# Hello_Bomi.net
KiCad netlist of a schematic drawn in EAGLE
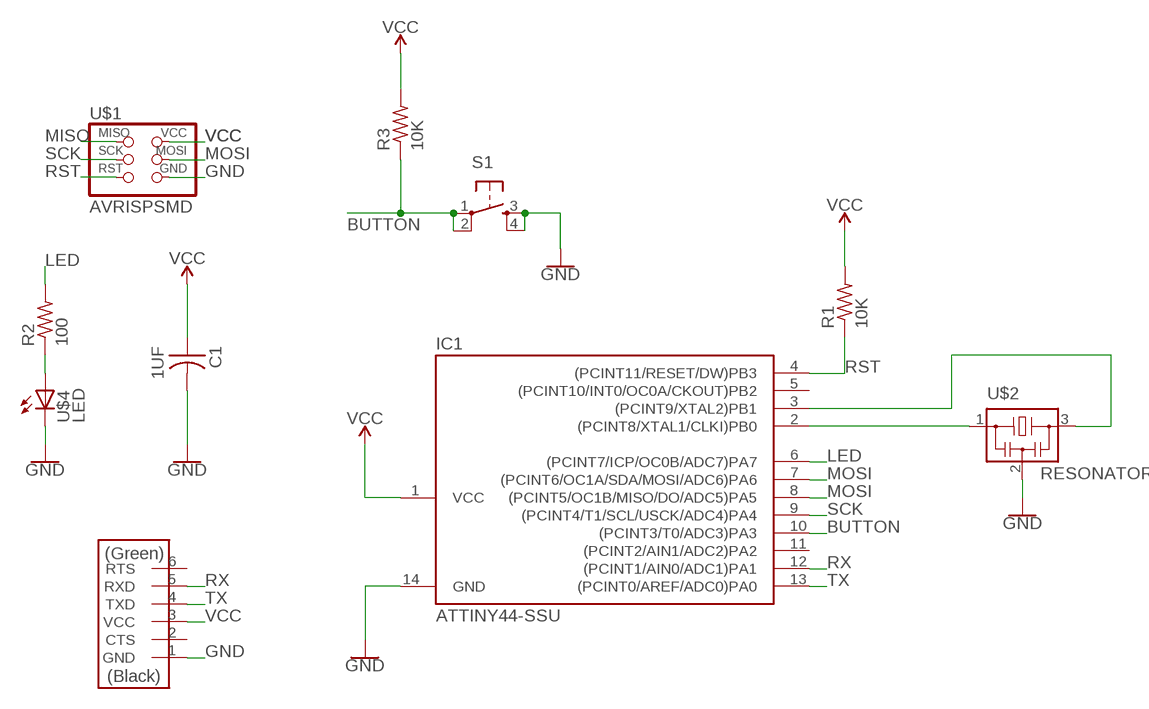
[diagram p0: schematic, sheet 1]

(export (version "E")
  (design (tool "Eeschema 10.0.6"))
  (components
    (comp (ref "C1")
      (value "1UF")
      (footprint "eagle-import:C1206FAB")
      (libsource (lib "eagle-import") (part "CAP-US1206FAB"))
    )
    (comp (ref "IC1")
      (value "ATTINY44-SSU")
      (footprint "eagle-import:SOIC14")
      (libsource (lib "eagle-import") (part "ATTINY44-SSU"))
    )
    (comp (ref "R1")
      (value "10K")
      (footprint "eagle-import:R1206FAB")
      (libsource (lib "eagle-import") (part "RES-US1206FAB"))
    )
    (comp (ref "R2")
      (value "100")
      (footprint "eagle-import:R1206FAB")
      (libsource (lib "eagle-import") (part "RES-US1206FAB"))
    )
    (comp (ref "R3")
      (value "10K")
      (footprint "eagle-import:R1206FAB")
      (libsource (lib "eagle-import") (part "RES-US1206FAB"))
    )
    (comp (ref "S1")
      (value "6MM_SWITCH6MM_SWITCH")
      (footprint "eagle-import:6MM_SWITCH")
      (libsource (lib "eagle-import") (part "6MM_SWITCH6MM_SWITCH"))
    )
    (comp (ref "U$1")
      (value "AVRISPSMD")
      (footprint "eagle-import:2X03SMD")
      (libsource (lib "eagle-import") (part "AVRISPSMD"))
    )
    (comp (ref "U$2")
      (value "RESONATOR")
      (footprint "eagle-import:EFOBM")
      (libsource (lib "eagle-import") (part "RESONATOR"))
    )
    (comp (ref "U$3")
      (value "FTDI-SMD-HEADER")
      (footprint "eagle-import:1X06SMD")
      (libsource (lib "eagle-import") (part "FTDI-SMD-HEADER"))
    )
    (comp (ref "U$4")
      (value "LED")
      (footprint "eagle-import:LED1206FAB")
      (libsource (lib "eagle-import") (part "LEDFAB1206"))
    )
  )
  (nets
    (net (code "1") (name "/BUTTON") (class "Default")
      (node (ref "IC1") (pin "10") (pinfunction "(PCINT3/T0/ADC3)PA3_10") (pintype "bidirectional"))
      (node (ref "R3") (pin "1") (pinfunction "1_1") (pintype "passive"))
      (node (ref "S1") (pin "1") (pinfunction "P_1") (pintype "passive"))
      (node (ref "S1") (pin "2") (pinfunction "P1_2") (pintype "passive"))
    )
    (net (code "2") (name "/LED") (class "Default")
      (node (ref "IC1") (pin "6") (pinfunction "(PCINT7/ICP/OC0B/ADC7)PA7_6") (pintype "bidirectional"))
      (node (ref "R2") (pin "2") (pinfunction "2_2") (pintype "passive"))
    )
    (net (code "3") (name "/MISO") (class "Default")
      (node (ref "U$1") (pin "1") (pinfunction "MISO_1") (pintype "passive"))
    )
    (net (code "4") (name "/MOSI") (class "Default")
      (node (ref "IC1") (pin "7") (pinfunction "(PCINT6/OC1A/SDA/MOSI/ADC6)PA6_7") (pintype "bidirectional"))
      (node (ref "IC1") (pin "8") (pinfunction "(PCINT5/OC1B/MISO/DO/ADC5)PA5_8") (pintype "bidirectional"))
      (node (ref "U$1") (pin "4") (pinfunction "MOSI_4") (pintype "passive"))
    )
    (net (code "5") (name "/RST") (class "Default")
      (node (ref "IC1") (pin "4") (pinfunction "(PCINT11/RESET/DW)PB3_4") (pintype "bidirectional"))
      (node (ref "R1") (pin "1") (pinfunction "1_1") (pintype "passive"))
      (node (ref "U$1") (pin "5") (pinfunction "RST_5") (pintype "passive"))
    )
    (net (code "6") (name "/RX") (class "Default")
      (node (ref "IC1") (pin "12") (pinfunction "(PCINT1/AIN0/ADC1)PA1_12") (pintype "bidirectional"))
      (node (ref "U$3") (pin "5") (pinfunction "RXD_5") (pintype "bidirectional"))
    )
    (net (code "7") (name "/SCK") (class "Default")
      (node (ref "IC1") (pin "9") (pinfunction "(PCINT4/T1/SCL/USCK/ADC4)PA4_9") (pintype "bidirectional"))
      (node (ref "U$1") (pin "3") (pinfunction "SCK_3") (pintype "passive"))
    )
    (net (code "8") (name "/TX") (class "Default")
      (node (ref "IC1") (pin "13") (pinfunction "(PCINT0/AREF/ADC0)PA0_13") (pintype "bidirectional"))
      (node (ref "U$3") (pin "4") (pinfunction "TXD_4") (pintype "bidirectional"))
    )
    (net (code "9") (name "GND") (class "Default")
      (node (ref "C1") (pin "2") (pinfunction "2_2") (pintype "passive"))
      (node (ref "IC1") (pin "14") (pinfunction "GND_14") (pintype "power_in"))
      (node (ref "S1") (pin "3") (pinfunction "S_3") (pintype "passive"))
      (node (ref "S1") (pin "4") (pinfunction "S1_4") (pintype "passive"))
      (node (ref "U$1") (pin "6") (pinfunction "GND_6") (pintype "passive"))
      (node (ref "U$2") (pin "2") (pinfunction "2_2") (pintype "passive"))
      (node (ref "U$3") (pin "1") (pinfunction "GND_1") (pintype "bidirectional"))
      (node (ref "U$4") (pin "2") (pinfunction "C_2") (pintype "passive"))
    )
    (net (code "10") (name "Net-(IC1-(PCINT8{slash}XTAL1{slash}CLKI)PB0)") (class "Default")
      (node (ref "IC1") (pin "2") (pinfunction "(PCINT8/XTAL1/CLKI)PB0_2") (pintype "bidirectional"))
      (node (ref "U$2") (pin "1") (pinfunction "1_1") (pintype "passive"))
    )
    (net (code "11") (name "Net-(IC1-(PCINT9{slash}XTAL2)PB1)") (class "Default")
      (node (ref "IC1") (pin "3") (pinfunction "(PCINT9/XTAL2)PB1_3") (pintype "bidirectional"))
      (node (ref "U$2") (pin "3") (pinfunction "3_3") (pintype "passive"))
    )
    (net (code "12") (name "Net-(U$4-A)") (class "Default")
      (node (ref "R2") (pin "1") (pinfunction "1_1") (pintype "passive"))
      (node (ref "U$4") (pin "1") (pinfunction "A_1") (pintype "passive"))
    )
    (net (code "13") (name "VCC") (class "Default")
      (node (ref "C1") (pin "1") (pinfunction "1_1") (pintype "passive"))
      (node (ref "IC1") (pin "1") (pinfunction "VCC_1") (pintype "power_in"))
      (node (ref "R1") (pin "2") (pinfunction "2_2") (pintype "passive"))
      (node (ref "R3") (pin "2") (pinfunction "2_2") (pintype "passive"))
      (node (ref "U$1") (pin "2") (pinfunction "VCC_2") (pintype "passive"))
      (node (ref "U$3") (pin "3") (pinfunction "VCC_3") (pintype "bidirectional"))
    )
    (net (code "14") (name "unconnected-(IC1-(PCINT2{slash}AIN1{slash}ADC2)PA2-Pad11)") (class "Default")
      (node (ref "IC1") (pin "11") (pinfunction "(PCINT2/AIN1/ADC2)PA2_11") (pintype "bidirectional"))
    )
    (net (code "15") (name "unconnected-(IC1-(PCINT10{slash}INT0{slash}OC0A{slash}CKOUT)PB2-Pad5)") (class "Default")
      (node (ref "IC1") (pin "5") (pinfunction "(PCINT10/INT0/OC0A/CKOUT)PB2_5") (pintype "bidirectional"))
    )
    (net (code "16") (name "unconnected-(U$3-CTS-Pad2)") (class "Default")
      (node (ref "U$3") (pin "2") (pinfunction "CTS_2") (pintype "bidirectional"))
    )
    (net (code "17") (name "unconnected-(U$3-RTS-Pad6)") (class "Default")
      (node (ref "U$3") (pin "6") (pinfunction "RTS_6") (pintype "bidirectional"))
    )
  )
)
